# sdram_xs.net
KiCad netlist of a schematic drawn in Altium Designer
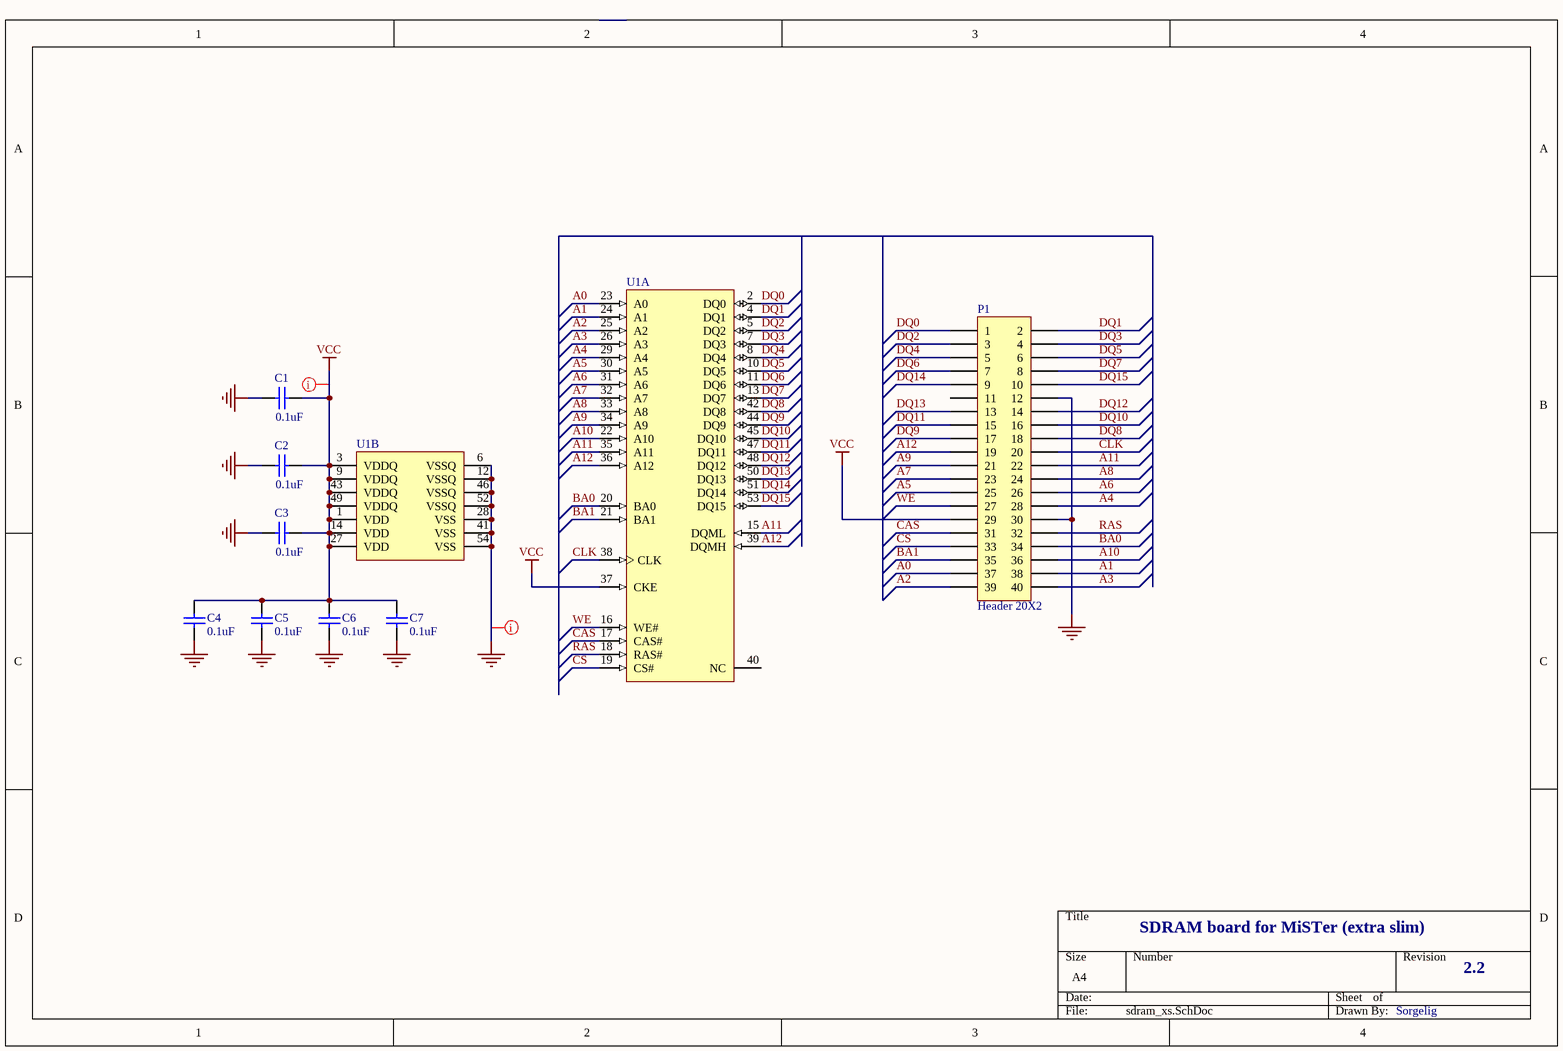
[diagram p0: sdram_xs.SchDoc]

(export (version "E")
  (design (tool "Eeschema 10.0.6"))
  (components
    (comp (ref "C1")
      (value "0.1uF")
      (footprint "C0805")
      (description "Ceramic Chip Capacitor - Standard")
      (fields (field (name "Comment") "C0805") (field (name "PUBLISHER") "Altium Limited"))
      (libsource (lib "lib") (part "C0805"))
    )
    (comp (ref "C2")
      (value "0.1uF")
      (footprint "C0805")
      (description "Ceramic Chip Capacitor - Standard")
      (fields (field (name "Comment") "C0805") (field (name "PUBLISHER") "Altium Limited"))
      (libsource (lib "lib") (part "C0805"))
    )
    (comp (ref "C3")
      (value "0.1uF")
      (footprint "C0805")
      (description "Ceramic Chip Capacitor - Standard")
      (fields (field (name "Comment") "+") (field (name "PUBLISHER") "Altium Limited"))
      (libsource (lib "lib") (part "C0805"))
    )
    (comp (ref "C4")
      (value "0.1uF")
      (footprint "C0805")
      (description "Ceramic Chip Capacitor - Standard")
      (fields (field (name "Comment") "C0805") (field (name "PUBLISHER") "Altium Limited"))
      (libsource (lib "lib") (part "C0805"))
    )
    (comp (ref "C5")
      (value "0.1uF")
      (footprint "C0805")
      (description "Ceramic Chip Capacitor - Standard")
      (fields (field (name "Comment") "+") (field (name "PUBLISHER") "Altium Limited"))
      (libsource (lib "lib") (part "C0805"))
    )
    (comp (ref "C6")
      (value "0.1uF")
      (footprint "C0805")
      (description "Ceramic Chip Capacitor - Standard")
      (fields (field (name "Comment") "+") (field (name "PUBLISHER") "Altium Limited"))
      (libsource (lib "lib") (part "C0805"))
    )
    (comp (ref "C7")
      (value "0.1uF")
      (footprint "C0805")
      (description "Ceramic Chip Capacitor - Standard")
      (fields (field (name "Comment") "+") (field (name "PUBLISHER") "Altium Limited"))
      (libsource (lib "lib") (part "C0805"))
    )
    (comp (ref "P1")
      (value "Header 20X2")
      (footprint "HDR20x2_90")
      (description "Header, 20-Pin, Dual row")
      (fields (field (name "PUBLISHER") "Altium Limited"))
      (libsource (lib "Miscellaneous Connectors") (part "Header 20X2"))
    )
    (comp (ref "U1")
      (value "~")
      (footprint "TSOP54")
      (description "256Mb SDR SDRAM, 16Mb x 16, 6ns, 3.3V, 54-Pin TSOP")
      (fields (field (name "VOLTAGE") "3.3V ") (field (name "MANUFACTURER") "Micron"))
      (libsource (lib "lib") (part "AS4C16M16SA-6TCN"))
    )
  )
  (nets
    (net (code "1") (name "/A0") (class "Default")
      (node (ref "P1") (pin "37") (pinfunction "37_37") (pintype "passive"))
      (node (ref "U1") (pin "23") (pinfunction "A0_23") (pintype "input"))
    )
    (net (code "2") (name "/A1") (class "Default")
      (node (ref "P1") (pin "38") (pinfunction "38_38") (pintype "passive"))
      (node (ref "U1") (pin "24") (pinfunction "A1_24") (pintype "input"))
    )
    (net (code "3") (name "/A2") (class "Default")
      (node (ref "P1") (pin "39") (pinfunction "39_39") (pintype "passive"))
      (node (ref "U1") (pin "25") (pinfunction "A2_25") (pintype "input"))
    )
    (net (code "4") (name "/A3") (class "Default")
      (node (ref "P1") (pin "40") (pinfunction "40_40") (pintype "passive"))
      (node (ref "U1") (pin "26") (pinfunction "A3_26") (pintype "input"))
    )
    (net (code "5") (name "/A4") (class "Default")
      (node (ref "P1") (pin "28") (pinfunction "28_28") (pintype "passive"))
      (node (ref "U1") (pin "29") (pinfunction "A4_29") (pintype "input"))
    )
    (net (code "6") (name "/A5") (class "Default")
      (node (ref "P1") (pin "25") (pinfunction "25_25") (pintype "passive"))
      (node (ref "U1") (pin "30") (pinfunction "A5_30") (pintype "input"))
    )
    (net (code "7") (name "/A6") (class "Default")
      (node (ref "P1") (pin "26") (pinfunction "26_26") (pintype "passive"))
      (node (ref "U1") (pin "31") (pinfunction "A6_31") (pintype "input"))
    )
    (net (code "8") (name "/A7") (class "Default")
      (node (ref "P1") (pin "23") (pinfunction "23_23") (pintype "passive"))
      (node (ref "U1") (pin "32") (pinfunction "A7_32") (pintype "input"))
    )
    (net (code "9") (name "/A8") (class "Default")
      (node (ref "P1") (pin "24") (pinfunction "24_24") (pintype "passive"))
      (node (ref "U1") (pin "33") (pinfunction "A8_33") (pintype "input"))
    )
    (net (code "10") (name "/A9") (class "Default")
      (node (ref "P1") (pin "21") (pinfunction "21_21") (pintype "passive"))
      (node (ref "U1") (pin "34") (pinfunction "A9_34") (pintype "input"))
    )
    (net (code "11") (name "/A10") (class "Default")
      (node (ref "P1") (pin "36") (pinfunction "36_36") (pintype "passive"))
      (node (ref "U1") (pin "22") (pinfunction "A10_22") (pintype "input"))
    )
    (net (code "12") (name "/A11") (class "Default")
      (node (ref "P1") (pin "22") (pinfunction "22_22") (pintype "passive"))
      (node (ref "U1") (pin "15") (pinfunction "DQML_15") (pintype "input"))
      (node (ref "U1") (pin "35") (pinfunction "A11_35") (pintype "input"))
    )
    (net (code "13") (name "/A12") (class "Default")
      (node (ref "P1") (pin "19") (pinfunction "19_19") (pintype "passive"))
      (node (ref "U1") (pin "36") (pinfunction "A12_36") (pintype "input"))
      (node (ref "U1") (pin "39") (pinfunction "DQMH_39") (pintype "input"))
    )
    (net (code "14") (name "/BA0") (class "Default")
      (node (ref "P1") (pin "34") (pinfunction "34_34") (pintype "passive"))
      (node (ref "U1") (pin "20") (pinfunction "BA0_20") (pintype "input"))
    )
    (net (code "15") (name "/BA1") (class "Default")
      (node (ref "P1") (pin "35") (pinfunction "35_35") (pintype "passive"))
      (node (ref "U1") (pin "21") (pinfunction "BA1_21") (pintype "input"))
    )
    (net (code "16") (name "/CAS") (class "Default")
      (node (ref "P1") (pin "31") (pinfunction "31_31") (pintype "passive"))
      (node (ref "U1") (pin "17") (pinfunction "CAS#_17") (pintype "input"))
    )
    (net (code "17") (name "/CLK") (class "Default")
      (node (ref "P1") (pin "20") (pinfunction "20_20") (pintype "passive"))
      (node (ref "U1") (pin "38") (pinfunction "CLK_38") (pintype "input"))
    )
    (net (code "18") (name "/CS") (class "Default")
      (node (ref "P1") (pin "33") (pinfunction "33_33") (pintype "passive"))
      (node (ref "U1") (pin "19") (pinfunction "CS#_19") (pintype "input"))
    )
    (net (code "19") (name "/DQ0") (class "Default")
      (node (ref "P1") (pin "1") (pinfunction "1_1") (pintype "passive"))
      (node (ref "U1") (pin "2") (pinfunction "DQ0_2") (pintype "bidirectional"))
    )
    (net (code "20") (name "/DQ1") (class "Default")
      (node (ref "P1") (pin "2") (pinfunction "2_2") (pintype "passive"))
      (node (ref "U1") (pin "4") (pinfunction "DQ1_4") (pintype "bidirectional"))
    )
    (net (code "21") (name "/DQ2") (class "Default")
      (node (ref "P1") (pin "3") (pinfunction "3_3") (pintype "passive"))
      (node (ref "U1") (pin "5") (pinfunction "DQ2_5") (pintype "bidirectional"))
    )
    (net (code "22") (name "/DQ3") (class "Default")
      (node (ref "P1") (pin "4") (pinfunction "4_4") (pintype "passive"))
      (node (ref "U1") (pin "7") (pinfunction "DQ3_7") (pintype "bidirectional"))
    )
    (net (code "23") (name "/DQ4") (class "Default")
      (node (ref "P1") (pin "5") (pinfunction "5_5") (pintype "passive"))
      (node (ref "U1") (pin "8") (pinfunction "DQ4_8") (pintype "bidirectional"))
    )
    (net (code "24") (name "/DQ5") (class "Default")
      (node (ref "P1") (pin "6") (pinfunction "6_6") (pintype "passive"))
      (node (ref "U1") (pin "10") (pinfunction "DQ5_10") (pintype "bidirectional"))
    )
    (net (code "25") (name "/DQ6") (class "Default")
      (node (ref "P1") (pin "7") (pinfunction "7_7") (pintype "passive"))
      (node (ref "U1") (pin "11") (pinfunction "DQ6_11") (pintype "bidirectional"))
    )
    (net (code "26") (name "/DQ7") (class "Default")
      (node (ref "P1") (pin "8") (pinfunction "8_8") (pintype "passive"))
      (node (ref "U1") (pin "13") (pinfunction "DQ7_13") (pintype "bidirectional"))
    )
    (net (code "27") (name "/DQ8") (class "Default")
      (node (ref "P1") (pin "18") (pinfunction "18_18") (pintype "passive"))
      (node (ref "U1") (pin "42") (pinfunction "DQ8_42") (pintype "bidirectional"))
    )
    (net (code "28") (name "/DQ9") (class "Default")
      (node (ref "P1") (pin "17") (pinfunction "17_17") (pintype "passive"))
      (node (ref "U1") (pin "44") (pinfunction "DQ9_44") (pintype "bidirectional"))
    )
    (net (code "29") (name "/DQ10") (class "Default")
      (node (ref "P1") (pin "16") (pinfunction "16_16") (pintype "passive"))
      (node (ref "U1") (pin "45") (pinfunction "DQ10_45") (pintype "bidirectional"))
    )
    (net (code "30") (name "/DQ11") (class "Default")
      (node (ref "P1") (pin "15") (pinfunction "15_15") (pintype "passive"))
      (node (ref "U1") (pin "47") (pinfunction "DQ11_47") (pintype "bidirectional"))
    )
    (net (code "31") (name "/DQ12") (class "Default")
      (node (ref "P1") (pin "14") (pinfunction "14_14") (pintype "passive"))
      (node (ref "U1") (pin "48") (pinfunction "DQ12_48") (pintype "bidirectional"))
    )
    (net (code "32") (name "/DQ13") (class "Default")
      (node (ref "P1") (pin "13") (pinfunction "13_13") (pintype "passive"))
      (node (ref "U1") (pin "50") (pinfunction "DQ13_50") (pintype "bidirectional"))
    )
    (net (code "33") (name "/DQ14") (class "Default")
      (node (ref "P1") (pin "9") (pinfunction "9_9") (pintype "passive"))
      (node (ref "U1") (pin "51") (pinfunction "DQ14_51") (pintype "bidirectional"))
    )
    (net (code "34") (name "/DQ15") (class "Default")
      (node (ref "P1") (pin "10") (pinfunction "10_10") (pintype "passive"))
      (node (ref "U1") (pin "53") (pinfunction "DQ15_53") (pintype "bidirectional"))
    )
    (net (code "35") (name "/RAS") (class "Default")
      (node (ref "P1") (pin "32") (pinfunction "32_32") (pintype "passive"))
      (node (ref "U1") (pin "18") (pinfunction "RAS#_18") (pintype "input"))
    )
    (net (code "36") (name "/WE") (class "Default")
      (node (ref "P1") (pin "27") (pinfunction "27_27") (pintype "passive"))
      (node (ref "U1") (pin "16") (pinfunction "WE#_16") (pintype "input"))
    )
    (net (code "37") (name "GND") (class "Default")
      (node (ref "C1") (pin "1") (pinfunction "1_1") (pintype "passive"))
      (node (ref "C2") (pin "1") (pinfunction "1_1") (pintype "passive"))
      (node (ref "C3") (pin "1") (pinfunction "1_1") (pintype "passive"))
      (node (ref "C4") (pin "1") (pinfunction "1_1") (pintype "passive"))
      (node (ref "C5") (pin "1") (pinfunction "1_1") (pintype "passive"))
      (node (ref "C6") (pin "1") (pinfunction "1_1") (pintype "passive"))
      (node (ref "C7") (pin "1") (pinfunction "1_1") (pintype "passive"))
      (node (ref "P1") (pin "12") (pinfunction "12_12") (pintype "power_in"))
      (node (ref "P1") (pin "30") (pinfunction "30_30") (pintype "power_in"))
      (node (ref "U1") (pin "12") (pinfunction "VSSQ_12") (pintype "power_in"))
      (node (ref "U1") (pin "28") (pinfunction "VSS_28") (pintype "power_in"))
      (node (ref "U1") (pin "41") (pinfunction "VSS_41") (pintype "power_in"))
      (node (ref "U1") (pin "46") (pinfunction "VSSQ_46") (pintype "power_in"))
      (node (ref "U1") (pin "52") (pinfunction "VSSQ_52") (pintype "power_in"))
      (node (ref "U1") (pin "54") (pinfunction "VSS_54") (pintype "power_in"))
      (node (ref "U1") (pin "6") (pinfunction "VSSQ_6") (pintype "power_in"))
    )
    (net (code "38") (name "VCC") (class "Default")
      (node (ref "C1") (pin "2") (pinfunction "2_2") (pintype "passive"))
      (node (ref "C2") (pin "2") (pinfunction "2_2") (pintype "passive"))
      (node (ref "C3") (pin "2") (pinfunction "2_2") (pintype "passive"))
      (node (ref "C4") (pin "2") (pinfunction "2_2") (pintype "passive"))
      (node (ref "C5") (pin "2") (pinfunction "2_2") (pintype "passive"))
      (node (ref "C6") (pin "2") (pinfunction "2_2") (pintype "passive"))
      (node (ref "C7") (pin "2") (pinfunction "2_2") (pintype "passive"))
      (node (ref "P1") (pin "29") (pinfunction "29_29") (pintype "power_in"))
      (node (ref "U1") (pin "1") (pinfunction "VDD_1") (pintype "power_in"))
      (node (ref "U1") (pin "14") (pinfunction "VDD_14") (pintype "power_in"))
      (node (ref "U1") (pin "27") (pinfunction "VDD_27") (pintype "power_in"))
      (node (ref "U1") (pin "3") (pinfunction "VDDQ_3") (pintype "power_in"))
      (node (ref "U1") (pin "37") (pinfunction "CKE_37") (pintype "input"))
      (node (ref "U1") (pin "43") (pinfunction "VDDQ_43") (pintype "power_in"))
      (node (ref "U1") (pin "49") (pinfunction "VDDQ_49") (pintype "power_in"))
      (node (ref "U1") (pin "9") (pinfunction "VDDQ_9") (pintype "power_in"))
    )
    (net (code "39") (name "unconnected-(P1-Pad11)") (class "Default")
      (node (ref "P1") (pin "11") (pinfunction "11_11") (pintype "power_in"))
    )
    (net (code "40") (name "unconnected-(U1A-NC-Pad40)") (class "Default")
      (node (ref "U1") (pin "40") (pinfunction "NC_40") (pintype "passive"))
    )
  )
)
